# SCH_SLV258-__2026-06-08.net
KiCad netlist of a schematic drawn in EasyEDA
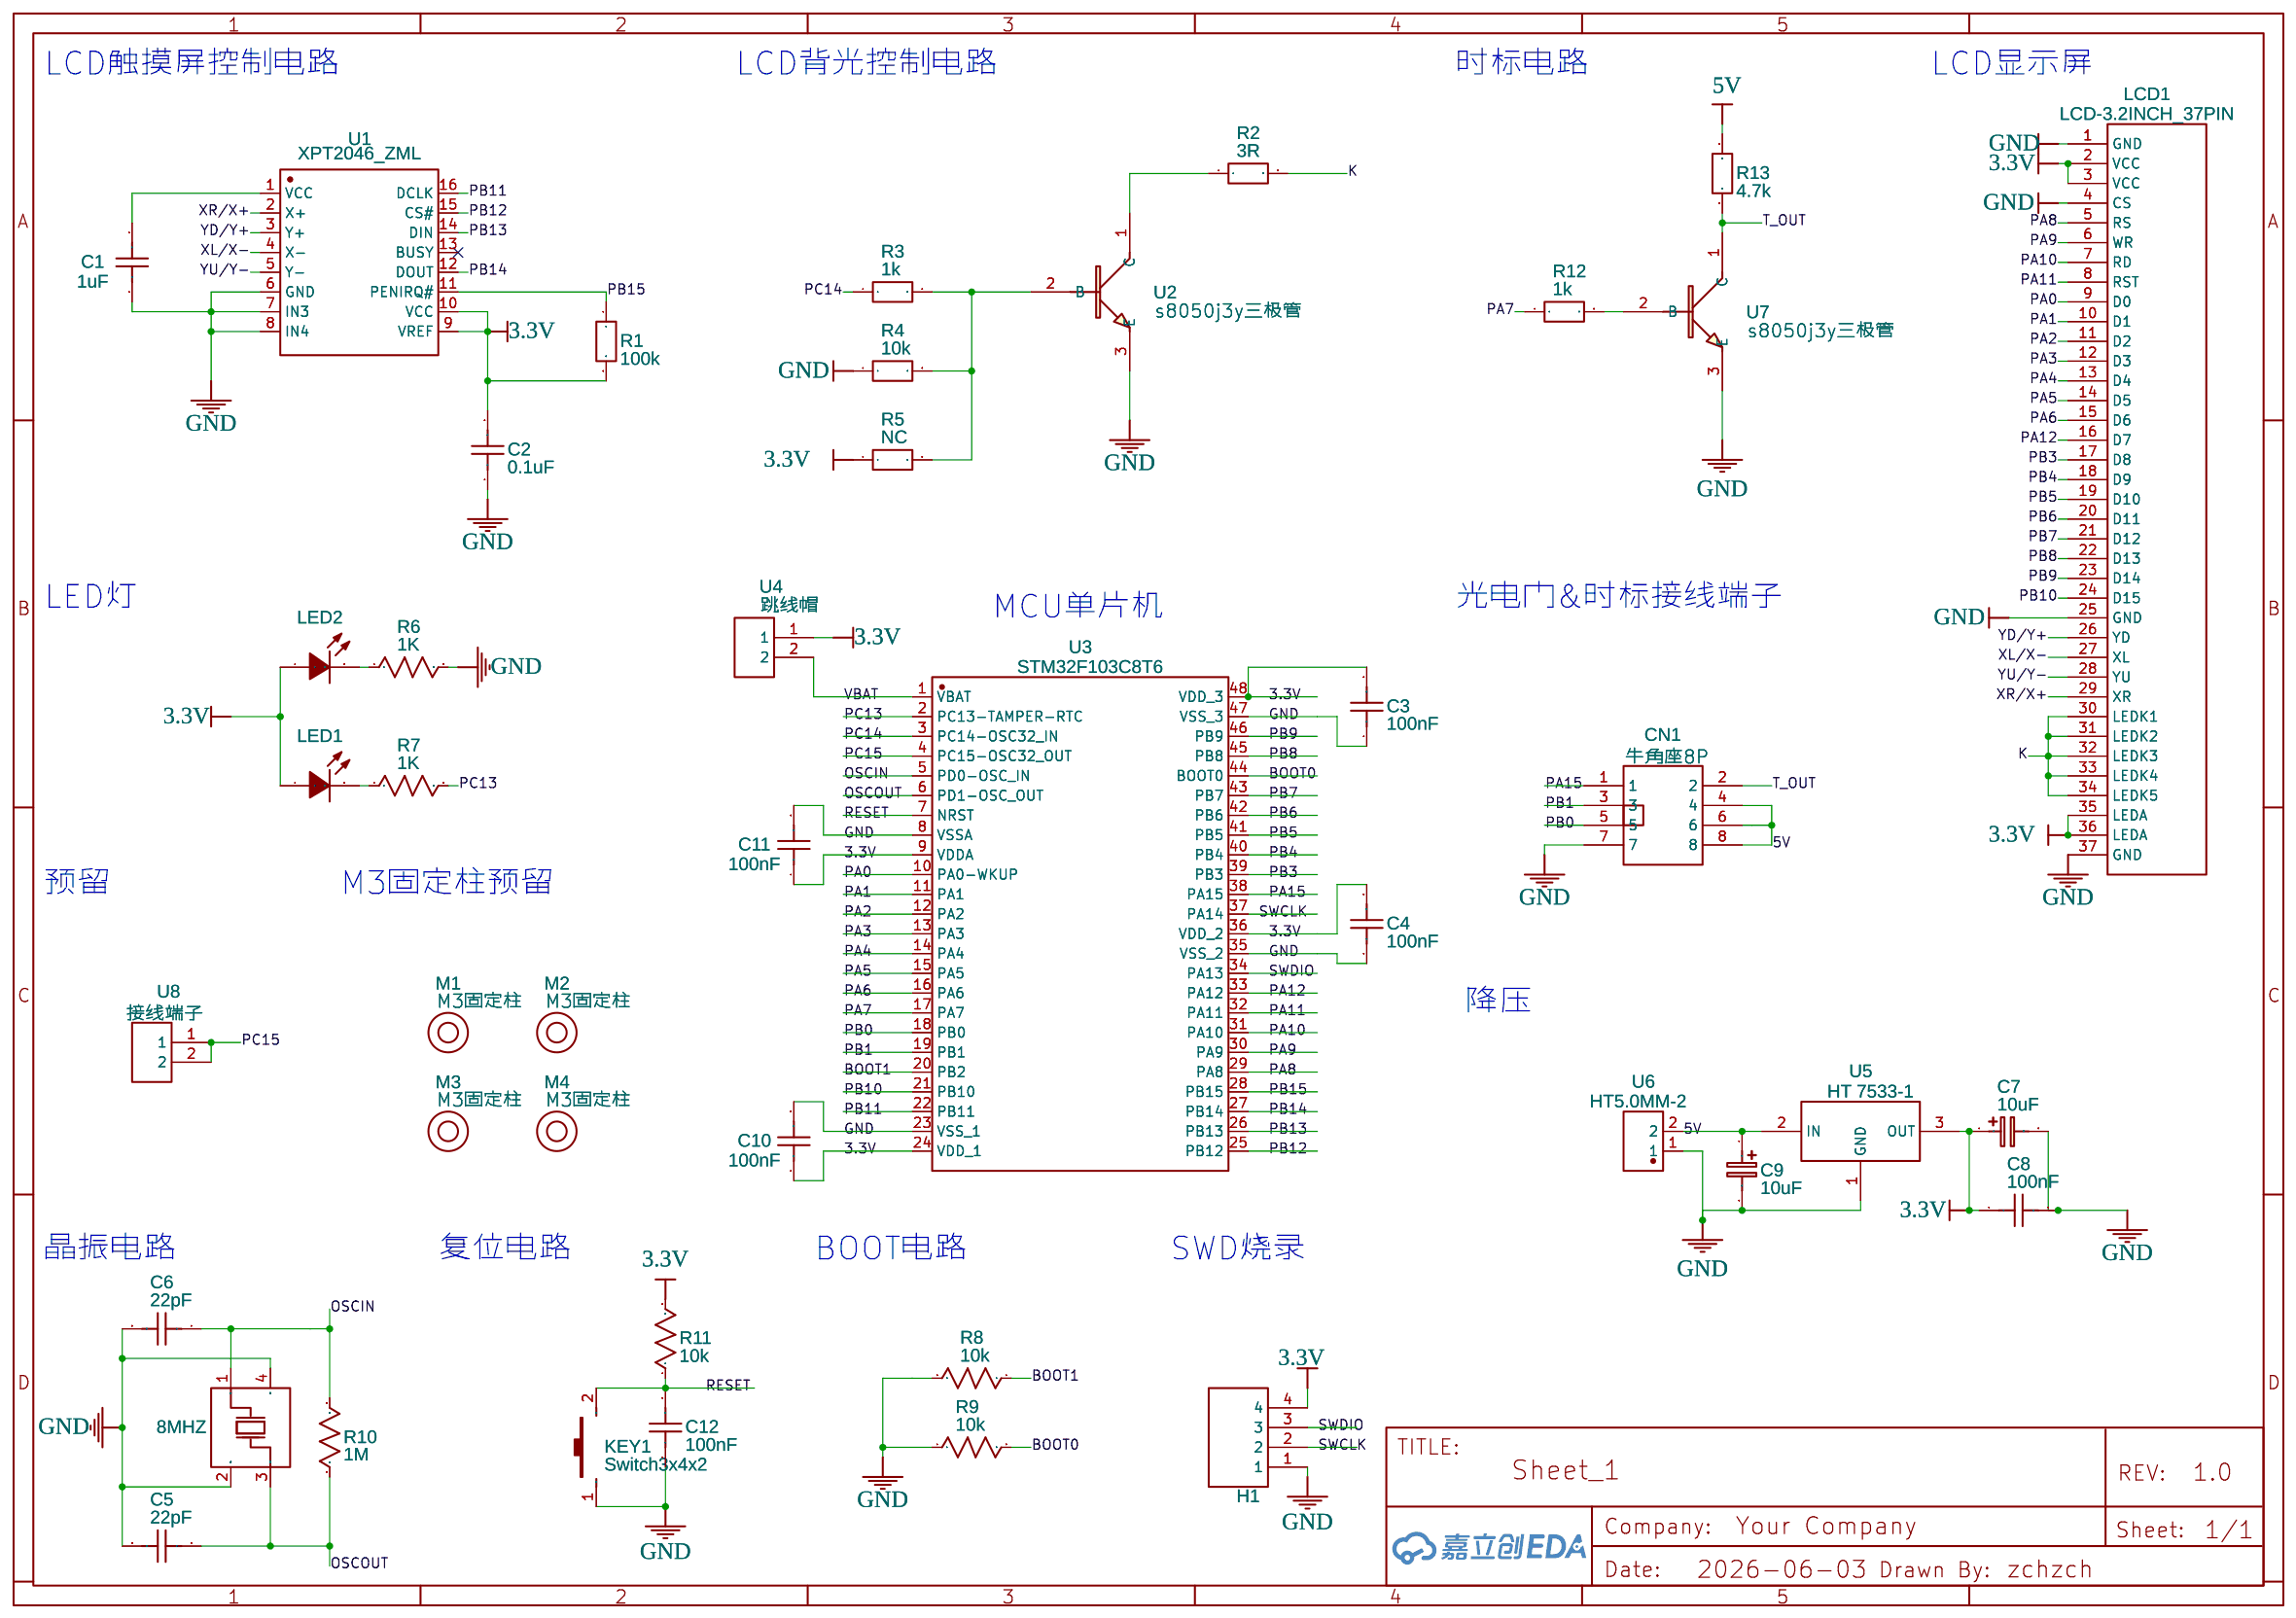
[diagram p0: schematic sheet]

(export (version "E")
  (design (tool "Eeschema 10.0.6"))
  (components
    (comp (ref "8MHZ")
      (value "3225-20MHZ-15PF-10PPM")
      (fields (field (name "Manufacturer") "TKD(泰晶)"))
      (libsource (lib "") (part "3225-20MHZ-15PF-10PPM"))
    )
    (comp (ref "C1") (value "1uF") (libsource (lib "") (part "C_0603_US")))
    (comp (ref "C2") (value "0.1uF") (libsource (lib "") (part "C_0603_US")))
    (comp (ref "C3") (value "100nF") (libsource (lib "") (part "C_0603_US")))
    (comp (ref "C4") (value "100nF") (libsource (lib "") (part "C_0603_US")))
    (comp (ref "C5") (value "22pF") (libsource (lib "") (part "Cap_RAD-0.1_US_1")))
    (comp (ref "C6") (value "22pF") (libsource (lib "") (part "Cap_RAD-0.1_US_1")))
    (comp (ref "C7") (value "10uF") (libsource (lib "") (part "C_Tan_SMD_A_EU_1")))
    (comp (ref "C8") (value "100nF") (libsource (lib "") (part "C_0603_US_1")))
    (comp (ref "C9") (value "10uF") (libsource (lib "") (part "C_Tan_SMD_A_EU")))
    (comp (ref "C10") (value "100nF") (libsource (lib "") (part "C_0603_US")))
    (comp (ref "C11") (value "100nF") (libsource (lib "") (part "C_0603_US")))
    (comp (ref "C12") (value "100nF") (libsource (lib "") (part "Cap_RAD-0.1_US")))
    (comp (ref "CN1") (value "牛角座8P") (libsource (lib "") (part "牛角座8P")))
    (comp (ref "H1")
      (value "220S-1*4P H=8.5MM Ytype Gold-plated")
      (fields (field (name "Manufacturer") "Ckmtw"))
      (libsource (lib "") (part "220S-1*4P H=8.5MM Ytype Gold-plated"))
    )
    (comp (ref "KEY1")
      (value "Switch3x4x2")
      (fields (field (name "Manufacturer") "ReliaPro"))
      (libsource (lib "") (part "Switch3x4x2"))
    )
    (comp (ref "LCD1") (value "LCD-3.2INCH_37PIN") (libsource (lib "") (part "LCD-3.2INCH_37PIN")))
    (comp (ref "LED1")
      (value "204-10SURD/S530-A3")
      (fields (field (name "Manufacturer") "EVERLIGHT"))
      (libsource (lib "") (part "204-10SURD/S530-A3"))
    )
    (comp (ref "LED2")
      (value "204-10SURD/S530-A3")
      (fields (field (name "Manufacturer") "EVERLIGHT"))
      (libsource (lib "") (part "204-10SURD/S530-A3"))
    )
    (comp (ref "M1") (value "M3固定柱") (libsource (lib "") (part "M3固定柱")))
    (comp (ref "M2") (value "M3固定柱") (libsource (lib "") (part "M3固定柱")))
    (comp (ref "M3") (value "M3固定柱") (libsource (lib "") (part "M3固定柱")))
    (comp (ref "M4") (value "M3固定柱") (libsource (lib "") (part "M3固定柱")))
    (comp (ref "R1") (value "100k") (libsource (lib "") (part "R_0603_EU_2")))
    (comp (ref "R2") (value "3R") (libsource (lib "") (part "R_0603_EU")))
    (comp (ref "R3") (value "1k") (libsource (lib "") (part "R_0603_EU")))
    (comp (ref "R4") (value "10k") (libsource (lib "") (part "R_0603_EU")))
    (comp (ref "R5") (value "NC") (libsource (lib "") (part "R_0603_EU")))
    (comp (ref "R6") (value "1K") (libsource (lib "") (part "Res_AXIAL-0.3(1/8W)_US")))
    (comp (ref "R7") (value "1K") (libsource (lib "") (part "Res_AXIAL-0.3(1/8W)_US")))
    (comp (ref "R8") (value "10k") (libsource (lib "") (part "Res_AXIAL-0.3(1/8W)_US_1")))
    (comp (ref "R9") (value "10k") (libsource (lib "") (part "Res_AXIAL-0.3(1/8W)_US")))
    (comp (ref "R10") (value "1M") (libsource (lib "") (part "Res_AXIAL-0.3(1/8W)_US_2")))
    (comp (ref "R11") (value "10k") (libsource (lib "") (part "Res_AXIAL-0.3(1/8W)_US_2")))
    (comp (ref "R12") (value "1k") (libsource (lib "") (part "R_0603_EU")))
    (comp (ref "R13") (value "4.7k") (libsource (lib "") (part "R_0603_EU_1")))
    (comp (ref "U1")
      (value "XPT2046_ZML")
      (fields (field (name "Manufacturer Part") "XPT2046") (field (name "Manufacturer") "XPT"))
      (libsource (lib "") (part "XPT2046_ZML"))
    )
    (comp (ref "U2") (value "s8050j3y三极管") (libsource (lib "") (part "j3y三极管")))
    (comp (ref "U3")
      (value "STM32F103C8T6")
      (fields (field (name "Manufacturer") "STMicroelectronics"))
      (libsource (lib "") (part "STM32F103C8T6"))
    )
    (comp (ref "U4") (value "跳线帽") (libsource (lib "") (part "跳线帽")))
    (comp (ref "U5") (value "HT 7533-1") (libsource (lib "") (part "HT 7533-1")))
    (comp (ref "U6")
      (value "HT5.0MM-2")
      (fields (field (name "Manufacturer Part") "HT3.96MM-2"))
      (libsource (lib "") (part "HT3.96MM-2"))
    )
    (comp (ref "U7") (value "s8050j3y三极管") (libsource (lib "") (part "j3y三极管")))
    (comp (ref "U8") (value "接线端子") (libsource (lib "") (part "跳线帽")))
  )
  (nets
    (net (code "1") (name "/BOOT0") (class "Default")
      (node (ref "R9") (pin "2") (pinfunction "2_2") (pintype "unspecified"))
      (node (ref "U3") (pin "44") (pinfunction "BOOT0_44") (pintype "unspecified"))
    )
    (net (code "2") (name "/BOOT1") (class "Default")
      (node (ref "R8") (pin "1") (pinfunction "1_1") (pintype "unspecified"))
      (node (ref "U3") (pin "20") (pinfunction "PB2_20") (pintype "unspecified"))
    )
    (net (code "3") (name "/K") (class "Default")
      (node (ref "LCD1") (pin "30") (pinfunction "LEDK1_30") (pintype "unspecified"))
      (node (ref "LCD1") (pin "31") (pinfunction "LEDK2_31") (pintype "unspecified"))
      (node (ref "LCD1") (pin "32") (pinfunction "LEDK3_32") (pintype "unspecified"))
      (node (ref "LCD1") (pin "33") (pinfunction "LEDK4_33") (pintype "unspecified"))
      (node (ref "LCD1") (pin "34") (pinfunction "LEDK5_34") (pintype "unspecified"))
      (node (ref "R2") (pin "2") (pinfunction "2_2") (pintype "unspecified"))
    )
    (net (code "4") (name "/OSCIN") (class "Default")
      (node (ref "8MHZ") (pin "1") (pinfunction "OSC1_1") (pintype "unspecified"))
      (node (ref "C6") (pin "1") (pinfunction "1_1") (pintype "unspecified"))
      (node (ref "R10") (pin "2") (pinfunction "2_2") (pintype "unspecified"))
      (node (ref "U3") (pin "5") (pinfunction "PD0-OSC_IN_5") (pintype "unspecified"))
    )
    (net (code "5") (name "/OSCOUT") (class "Default")
      (node (ref "8MHZ") (pin "3") (pinfunction "OSC2_3") (pintype "unspecified"))
      (node (ref "C5") (pin "1") (pinfunction "1_1") (pintype "unspecified"))
      (node (ref "R10") (pin "1") (pinfunction "1_1") (pintype "unspecified"))
      (node (ref "U3") (pin "6") (pinfunction "PD1-OSC_OUT_6") (pintype "unspecified"))
    )
    (net (code "6") (name "/PA0") (class "Default")
      (node (ref "LCD1") (pin "9") (pinfunction "D0_9") (pintype "unspecified"))
      (node (ref "U3") (pin "10") (pinfunction "PA0-WKUP_10") (pintype "unspecified"))
    )
    (net (code "7") (name "/PA1") (class "Default")
      (node (ref "LCD1") (pin "10") (pinfunction "D1_10") (pintype "unspecified"))
      (node (ref "U3") (pin "11") (pinfunction "PA1_11") (pintype "unspecified"))
    )
    (net (code "8") (name "/PA2") (class "Default")
      (node (ref "LCD1") (pin "11") (pinfunction "D2_11") (pintype "unspecified"))
      (node (ref "U3") (pin "12") (pinfunction "PA2_12") (pintype "unspecified"))
    )
    (net (code "9") (name "/PA3") (class "Default")
      (node (ref "LCD1") (pin "12") (pinfunction "D3_12") (pintype "unspecified"))
      (node (ref "U3") (pin "13") (pinfunction "PA3_13") (pintype "unspecified"))
    )
    (net (code "10") (name "/PA4") (class "Default")
      (node (ref "LCD1") (pin "13") (pinfunction "D4_13") (pintype "unspecified"))
      (node (ref "U3") (pin "14") (pinfunction "PA4_14") (pintype "unspecified"))
    )
    (net (code "11") (name "/PA5") (class "Default")
      (node (ref "LCD1") (pin "14") (pinfunction "D5_14") (pintype "unspecified"))
      (node (ref "U3") (pin "15") (pinfunction "PA5_15") (pintype "unspecified"))
    )
    (net (code "12") (name "/PA6") (class "Default")
      (node (ref "LCD1") (pin "15") (pinfunction "D6_15") (pintype "unspecified"))
      (node (ref "U3") (pin "16") (pinfunction "PA6_16") (pintype "unspecified"))
    )
    (net (code "13") (name "/PA7") (class "Default")
      (node (ref "R12") (pin "1") (pinfunction "1_1") (pintype "unspecified"))
      (node (ref "U3") (pin "17") (pinfunction "PA7_17") (pintype "unspecified"))
    )
    (net (code "14") (name "/PA8") (class "Default")
      (node (ref "LCD1") (pin "5") (pinfunction "RS_5") (pintype "unspecified"))
      (node (ref "U3") (pin "29") (pinfunction "PA8_29") (pintype "unspecified"))
    )
    (net (code "15") (name "/PA9") (class "Default")
      (node (ref "LCD1") (pin "6") (pinfunction "WR_6") (pintype "unspecified"))
      (node (ref "U3") (pin "30") (pinfunction "PA9_30") (pintype "unspecified"))
    )
    (net (code "16") (name "/PA10") (class "Default")
      (node (ref "LCD1") (pin "7") (pinfunction "RD_7") (pintype "unspecified"))
      (node (ref "U3") (pin "31") (pinfunction "PA10_31") (pintype "unspecified"))
    )
    (net (code "17") (name "/PA11") (class "Default")
      (node (ref "LCD1") (pin "8") (pinfunction "RST_8") (pintype "unspecified"))
      (node (ref "U3") (pin "32") (pinfunction "PA11_32") (pintype "unspecified"))
    )
    (net (code "18") (name "/PA12") (class "Default")
      (node (ref "LCD1") (pin "16") (pinfunction "D7_16") (pintype "unspecified"))
      (node (ref "U3") (pin "33") (pinfunction "PA12_33") (pintype "unspecified"))
    )
    (net (code "19") (name "/PA15") (class "Default")
      (node (ref "CN1") (pin "1") (pinfunction "1_1") (pintype "unspecified"))
      (node (ref "U3") (pin "38") (pinfunction "PA15_38") (pintype "unspecified"))
    )
    (net (code "20") (name "/PB0") (class "Default")
      (node (ref "CN1") (pin "5") (pinfunction "5_5") (pintype "unspecified"))
      (node (ref "U3") (pin "18") (pinfunction "PB0_18") (pintype "unspecified"))
    )
    (net (code "21") (name "/PB1") (class "Default")
      (node (ref "CN1") (pin "3") (pinfunction "3_3") (pintype "unspecified"))
      (node (ref "U3") (pin "19") (pinfunction "PB1_19") (pintype "unspecified"))
    )
    (net (code "22") (name "/PB3") (class "Default")
      (node (ref "LCD1") (pin "17") (pinfunction "D8_17") (pintype "unspecified"))
      (node (ref "U3") (pin "39") (pinfunction "PB3_39") (pintype "unspecified"))
    )
    (net (code "23") (name "/PB4") (class "Default")
      (node (ref "LCD1") (pin "18") (pinfunction "D9_18") (pintype "unspecified"))
      (node (ref "U3") (pin "40") (pinfunction "PB4_40") (pintype "unspecified"))
    )
    (net (code "24") (name "/PB5") (class "Default")
      (node (ref "LCD1") (pin "19") (pinfunction "D10_19") (pintype "unspecified"))
      (node (ref "U3") (pin "41") (pinfunction "PB5_41") (pintype "unspecified"))
    )
    (net (code "25") (name "/PB6") (class "Default")
      (node (ref "LCD1") (pin "20") (pinfunction "D11_20") (pintype "unspecified"))
      (node (ref "U3") (pin "42") (pinfunction "PB6_42") (pintype "unspecified"))
    )
    (net (code "26") (name "/PB7") (class "Default")
      (node (ref "LCD1") (pin "21") (pinfunction "D12_21") (pintype "unspecified"))
      (node (ref "U3") (pin "43") (pinfunction "PB7_43") (pintype "unspecified"))
    )
    (net (code "27") (name "/PB8") (class "Default")
      (node (ref "LCD1") (pin "22") (pinfunction "D13_22") (pintype "unspecified"))
      (node (ref "U3") (pin "45") (pinfunction "PB8_45") (pintype "unspecified"))
    )
    (net (code "28") (name "/PB9") (class "Default")
      (node (ref "LCD1") (pin "23") (pinfunction "D14_23") (pintype "unspecified"))
      (node (ref "U3") (pin "46") (pinfunction "PB9_46") (pintype "unspecified"))
    )
    (net (code "29") (name "/PB10") (class "Default")
      (node (ref "LCD1") (pin "24") (pinfunction "D15_24") (pintype "unspecified"))
      (node (ref "U3") (pin "21") (pinfunction "PB10_21") (pintype "unspecified"))
    )
    (net (code "30") (name "/PB11") (class "Default")
      (node (ref "U1") (pin "16") (pinfunction "DCLK_16") (pintype "unspecified"))
      (node (ref "U3") (pin "22") (pinfunction "PB11_22") (pintype "unspecified"))
    )
    (net (code "31") (name "/PB12") (class "Default")
      (node (ref "U1") (pin "15") (pinfunction "CS#_15") (pintype "unspecified"))
      (node (ref "U3") (pin "25") (pinfunction "PB12_25") (pintype "unspecified"))
    )
    (net (code "32") (name "/PB13") (class "Default")
      (node (ref "U1") (pin "14") (pinfunction "DIN_14") (pintype "unspecified"))
      (node (ref "U3") (pin "26") (pinfunction "PB13_26") (pintype "unspecified"))
    )
    (net (code "33") (name "/PB14") (class "Default")
      (node (ref "U1") (pin "12") (pinfunction "DOUT_12") (pintype "unspecified"))
      (node (ref "U3") (pin "27") (pinfunction "PB14_27") (pintype "unspecified"))
    )
    (net (code "34") (name "/PB15") (class "Default")
      (node (ref "R1") (pin "1") (pinfunction "1_1") (pintype "unspecified"))
      (node (ref "U1") (pin "11") (pinfunction "PENIRQ#_11") (pintype "unspecified"))
      (node (ref "U3") (pin "28") (pinfunction "PB15_28") (pintype "unspecified"))
    )
    (net (code "35") (name "/PC13") (class "Default")
      (node (ref "R7") (pin "2") (pinfunction "2_2") (pintype "unspecified"))
      (node (ref "U3") (pin "2") (pinfunction "PC13-TAMPER-RTC_2") (pintype "unspecified"))
    )
    (net (code "36") (name "/PC14") (class "Default")
      (node (ref "R3") (pin "1") (pinfunction "1_1") (pintype "unspecified"))
      (node (ref "U3") (pin "3") (pinfunction "PC14-OSC32_IN_3") (pintype "unspecified"))
    )
    (net (code "37") (name "/PC15") (class "Default")
      (node (ref "U3") (pin "4") (pinfunction "PC15-OSC32_OUT_4") (pintype "unspecified"))
      (node (ref "U8") (pin "1") (pinfunction "1_1") (pintype "unspecified"))
      (node (ref "U8") (pin "2") (pinfunction "2_2") (pintype "unspecified"))
    )
    (net (code "38") (name "/RESET") (class "Default")
      (node (ref "C12") (pin "2") (pinfunction "2_2") (pintype "unspecified"))
      (node (ref "KEY1") (pin "2") (pinfunction "2_2") (pintype "input"))
      (node (ref "R11") (pin "1") (pinfunction "1_1") (pintype "unspecified"))
      (node (ref "U3") (pin "7") (pinfunction "NRST_7") (pintype "unspecified"))
    )
    (net (code "39") (name "/SWCLK") (class "Default")
      (node (ref "H1") (pin "2") (pinfunction "2_2") (pintype "unspecified"))
      (node (ref "U3") (pin "37") (pinfunction "PA14_37") (pintype "unspecified"))
    )
    (net (code "40") (name "/SWDIO") (class "Default")
      (node (ref "H1") (pin "3") (pinfunction "3_3") (pintype "unspecified"))
      (node (ref "U3") (pin "34") (pinfunction "PA13_34") (pintype "unspecified"))
    )
    (net (code "41") (name "/T_OUT") (class "Default")
      (node (ref "CN1") (pin "2") (pinfunction "2_2") (pintype "unspecified"))
      (node (ref "R13") (pin "1") (pinfunction "1_1") (pintype "unspecified"))
      (node (ref "U7") (pin "1") (pinfunction "C_1") (pintype "unspecified"))
    )
    (net (code "42") (name "/VBAT") (class "Default")
      (node (ref "U3") (pin "1") (pinfunction "VBAT_1") (pintype "unspecified"))
      (node (ref "U4") (pin "2") (pinfunction "2_2") (pintype "unspecified"))
    )
    (net (code "43") (name "/XL{slash}X-") (class "Default")
      (node (ref "LCD1") (pin "27") (pinfunction "XL_27") (pintype "unspecified"))
      (node (ref "U1") (pin "4") (pinfunction "X-_4") (pintype "unspecified"))
    )
    (net (code "44") (name "/XR{slash}X+") (class "Default")
      (node (ref "LCD1") (pin "29") (pinfunction "XR_29") (pintype "unspecified"))
      (node (ref "U1") (pin "2") (pinfunction "X+_2") (pintype "unspecified"))
    )
    (net (code "45") (name "/YD{slash}Y+") (class "Default")
      (node (ref "LCD1") (pin "26") (pinfunction "YD_26") (pintype "unspecified"))
      (node (ref "U1") (pin "3") (pinfunction "Y+_3") (pintype "unspecified"))
    )
    (net (code "46") (name "/YU{slash}Y-") (class "Default")
      (node (ref "LCD1") (pin "28") (pinfunction "YU_28") (pintype "unspecified"))
      (node (ref "U1") (pin "5") (pinfunction "Y-_5") (pintype "unspecified"))
    )
    (net (code "47") (name "3.3V") (class "Default")
      (node (ref "C10") (pin "1") (pinfunction "1_1") (pintype "unspecified"))
      (node (ref "C11") (pin "1") (pinfunction "1_1") (pintype "unspecified"))
      (node (ref "C2") (pin "2") (pinfunction "2_2") (pintype "unspecified"))
      (node (ref "C3") (pin "2") (pinfunction "2_2") (pintype "unspecified"))
      (node (ref "C4") (pin "2") (pinfunction "2_2") (pintype "unspecified"))
      (node (ref "C7") (pin "1") (pinfunction "1_1") (pintype "unspecified"))
      (node (ref "C8") (pin "1") (pinfunction "1_1") (pintype "unspecified"))
      (node (ref "H1") (pin "4") (pinfunction "4_4") (pintype "unspecified"))
      (node (ref "LCD1") (pin "2") (pinfunction "VCC_2") (pintype "unspecified"))
      (node (ref "LCD1") (pin "3") (pinfunction "VCC_3") (pintype "unspecified"))
      (node (ref "LCD1") (pin "35") (pinfunction "LEDA_35") (pintype "unspecified"))
      (node (ref "LCD1") (pin "36") (pinfunction "LEDA_36") (pintype "unspecified"))
      (node (ref "LED1") (pin "1") (pinfunction "A_1") (pintype "unspecified"))
      (node (ref "LED2") (pin "1") (pinfunction "A_1") (pintype "unspecified"))
      (node (ref "R1") (pin "2") (pinfunction "2_2") (pintype "unspecified"))
      (node (ref "R11") (pin "2") (pinfunction "2_2") (pintype "unspecified"))
      (node (ref "R5") (pin "1") (pinfunction "1_1") (pintype "unspecified"))
      (node (ref "U1") (pin "10") (pinfunction "VCC_10") (pintype "unspecified"))
      (node (ref "U1") (pin "9") (pinfunction "VREF_9") (pintype "unspecified"))
      (node (ref "U3") (pin "24") (pinfunction "VDD_1_24") (pintype "unspecified"))
      (node (ref "U3") (pin "36") (pinfunction "VDD_2_36") (pintype "unspecified"))
      (node (ref "U3") (pin "48") (pinfunction "VDD_3_48") (pintype "unspecified"))
      (node (ref "U3") (pin "9") (pinfunction "VDDA_9") (pintype "unspecified"))
      (node (ref "U4") (pin "1") (pinfunction "1_1") (pintype "unspecified"))
      (node (ref "U5") (pin "3") (pinfunction "OUT_3") (pintype "unspecified"))
    )
    (net (code "48") (name "5V") (class "Default")
      (node (ref "C9") (pin "1") (pinfunction "1_1") (pintype "unspecified"))
      (node (ref "CN1") (pin "4") (pinfunction "4_4") (pintype "unspecified"))
      (node (ref "CN1") (pin "6") (pinfunction "6_6") (pintype "unspecified"))
      (node (ref "CN1") (pin "8") (pinfunction "8_8") (pintype "unspecified"))
      (node (ref "R13") (pin "2") (pinfunction "2_2") (pintype "unspecified"))
      (node (ref "U5") (pin "2") (pinfunction "IN_2") (pintype "unspecified"))
      (node (ref "U6") (pin "2") (pinfunction "2_2") (pintype "unspecified"))
    )
    (net (code "49") (name "GND") (class "Default")
      (node (ref "8MHZ") (pin "2") (pinfunction "GND_2") (pintype "unspecified"))
      (node (ref "8MHZ") (pin "4") (pinfunction "GND_4") (pintype "unspecified"))
      (node (ref "C1") (pin "1") (pinfunction "1_1") (pintype "unspecified"))
      (node (ref "C10") (pin "2") (pinfunction "2_2") (pintype "unspecified"))
      (node (ref "C11") (pin "2") (pinfunction "2_2") (pintype "unspecified"))
      (node (ref "C12") (pin "1") (pinfunction "1_1") (pintype "unspecified"))
      (node (ref "C2") (pin "1") (pinfunction "1_1") (pintype "unspecified"))
      (node (ref "C3") (pin "1") (pinfunction "1_1") (pintype "unspecified"))
      (node (ref "C4") (pin "1") (pinfunction "1_1") (pintype "unspecified"))
      (node (ref "C5") (pin "2") (pinfunction "2_2") (pintype "unspecified"))
      (node (ref "C6") (pin "2") (pinfunction "2_2") (pintype "unspecified"))
      (node (ref "C7") (pin "2") (pinfunction "2_2") (pintype "unspecified"))
      (node (ref "C8") (pin "2") (pinfunction "2_2") (pintype "unspecified"))
      (node (ref "C9") (pin "2") (pinfunction "2_2") (pintype "unspecified"))
      (node (ref "CN1") (pin "7") (pinfunction "7_7") (pintype "unspecified"))
      (node (ref "H1") (pin "1") (pinfunction "1_1") (pintype "unspecified"))
      (node (ref "KEY1") (pin "1") (pinfunction "1_1") (pintype "input"))
      (node (ref "LCD1") (pin "1") (pinfunction "GND_1") (pintype "unspecified"))
      (node (ref "LCD1") (pin "25") (pinfunction "GND_25") (pintype "unspecified"))
      (node (ref "LCD1") (pin "37") (pinfunction "GND_37") (pintype "unspecified"))
      (node (ref "LCD1") (pin "4") (pinfunction "CS_4") (pintype "unspecified"))
      (node (ref "R4") (pin "1") (pinfunction "1_1") (pintype "unspecified"))
      (node (ref "R6") (pin "2") (pinfunction "2_2") (pintype "unspecified"))
      (node (ref "R8") (pin "2") (pinfunction "2_2") (pintype "unspecified"))
      (node (ref "R9") (pin "1") (pinfunction "1_1") (pintype "unspecified"))
      (node (ref "U1") (pin "6") (pinfunction "GND_6") (pintype "unspecified"))
      (node (ref "U1") (pin "7") (pinfunction "IN3_7") (pintype "unspecified"))
      (node (ref "U1") (pin "8") (pinfunction "IN4_8") (pintype "unspecified"))
      (node (ref "U2") (pin "3") (pinfunction "E_3") (pintype "unspecified"))
      (node (ref "U3") (pin "23") (pinfunction "VSS_1_23") (pintype "unspecified"))
      (node (ref "U3") (pin "35") (pinfunction "VSS_2_35") (pintype "unspecified"))
      (node (ref "U3") (pin "47") (pinfunction "VSS_3_47") (pintype "unspecified"))
      (node (ref "U3") (pin "8") (pinfunction "VSSA_8") (pintype "unspecified"))
      (node (ref "U5") (pin "1") (pinfunction "GND_1") (pintype "unspecified"))
      (node (ref "U6") (pin "1") (pinfunction "1_1") (pintype "unspecified"))
      (node (ref "U7") (pin "3") (pinfunction "E_3") (pintype "unspecified"))
    )
    (net (code "50") (name "Net-(C1-Pad2)") (class "Default")
      (node (ref "C1") (pin "2") (pinfunction "2_2") (pintype "unspecified"))
      (node (ref "U1") (pin "1") (pinfunction "VCC_1") (pintype "unspecified"))
    )
    (net (code "51") (name "Net-(LED1-K)") (class "Default")
      (node (ref "LED1") (pin "2") (pinfunction "K_2") (pintype "unspecified"))
      (node (ref "R7") (pin "1") (pinfunction "1_1") (pintype "unspecified"))
    )
    (net (code "52") (name "Net-(LED2-K)") (class "Default")
      (node (ref "LED2") (pin "2") (pinfunction "K_2") (pintype "unspecified"))
      (node (ref "R6") (pin "1") (pinfunction "1_1") (pintype "unspecified"))
    )
    (net (code "53") (name "Net-(U2-B)") (class "Default")
      (node (ref "R3") (pin "2") (pinfunction "2_2") (pintype "unspecified"))
      (node (ref "R4") (pin "2") (pinfunction "2_2") (pintype "unspecified"))
      (node (ref "R5") (pin "2") (pinfunction "2_2") (pintype "unspecified"))
      (node (ref "U2") (pin "2") (pinfunction "B_2") (pintype "unspecified"))
    )
    (net (code "54") (name "Net-(U2-C)") (class "Default")
      (node (ref "R2") (pin "1") (pinfunction "1_1") (pintype "unspecified"))
      (node (ref "U2") (pin "1") (pinfunction "C_1") (pintype "unspecified"))
    )
    (net (code "55") (name "Net-(U7-B)") (class "Default")
      (node (ref "R12") (pin "2") (pinfunction "2_2") (pintype "unspecified"))
      (node (ref "U7") (pin "2") (pinfunction "B_2") (pintype "unspecified"))
    )
    (net (code "56") (name "unconnected-(U1-BUSY-Pad13)") (class "Default")
      (node (ref "U1") (pin "13") (pinfunction "BUSY_13") (pintype "unspecified+no_connect"))
    )
  )
)
